# MedidorCO2_ver2.net
KiCad netlist of a schematic drawn in Altium Designer
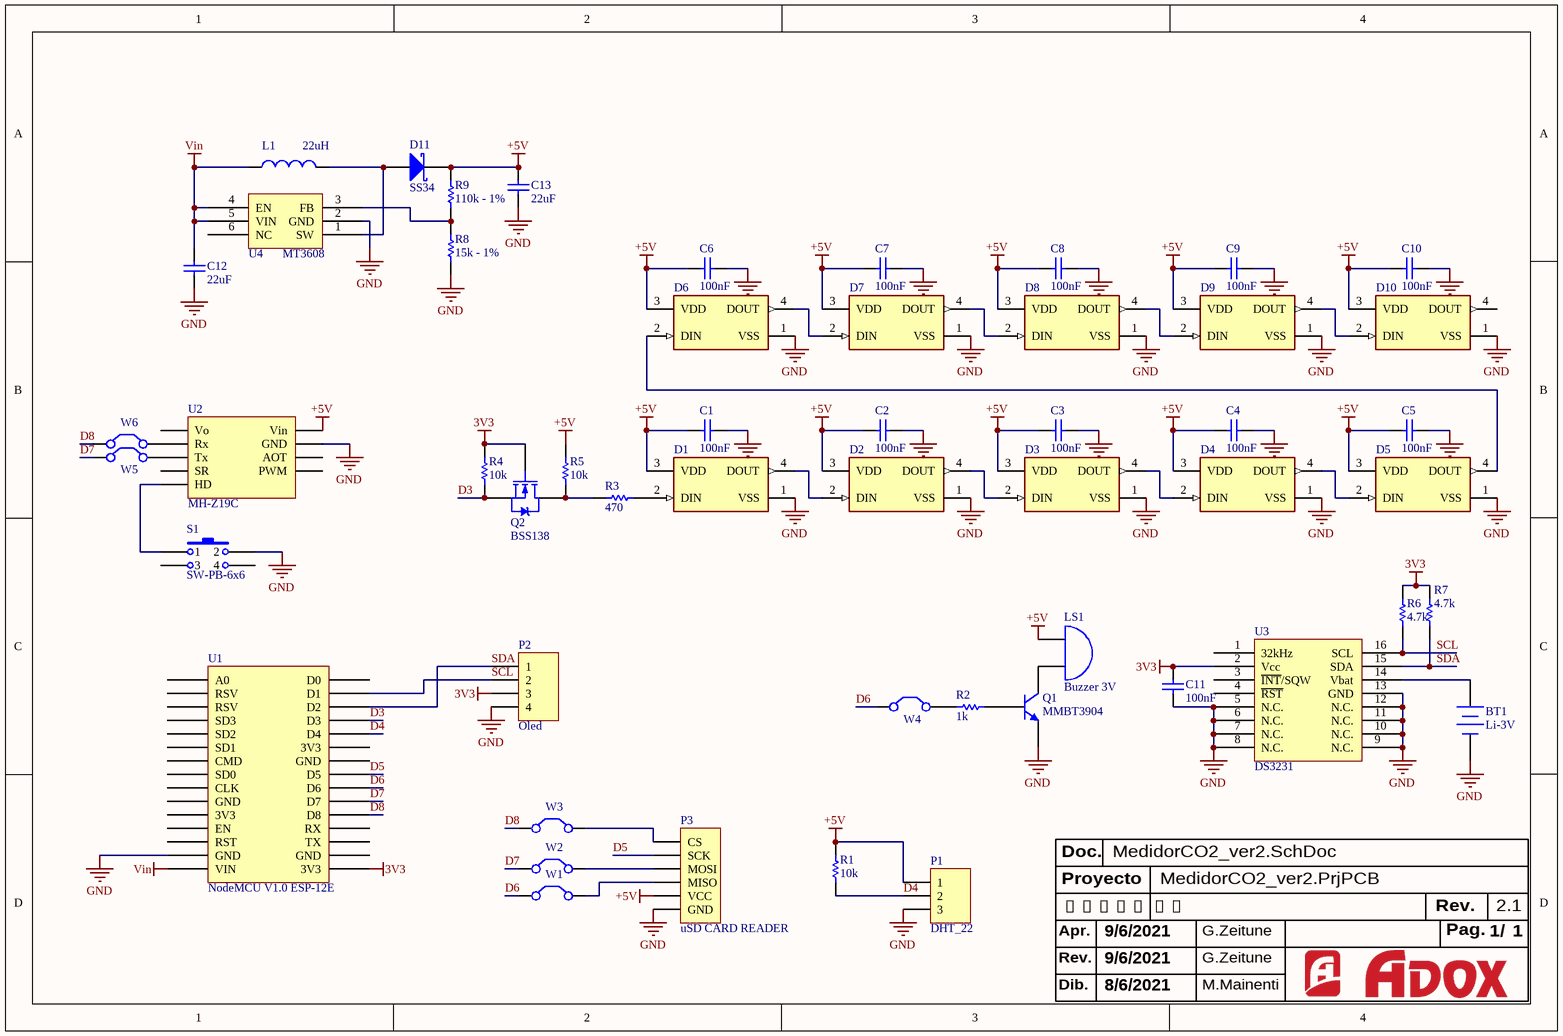
[diagram p0: MedidorCO2_ver2.SchDoc]

(export (version "E")
  (design (tool "Eeschema 10.0.6"))
  (components
    (comp (ref "BT1")
      (value "Li-3V")
      (footprint "BAT_LI_3V")
      (description "Multicell Battery")
      (fields (field (name "PUBLISHER") "Altium Limited"))
      (libsource (lib "Miscellaneous Devices") (part "Battery"))
    )
    (comp (ref "C1")
      (value "100nF")
      (footprint "CAPC2012N")
      (description "Capacitor (Semiconductor SIM Model)")
      (fields (field (name "PUBLISHER") "Altium Limited"))
      (libsource (lib "Miscellaneous Devices") (part "Cap Semi"))
    )
    (comp (ref "C2")
      (value "100nF")
      (footprint "CAPC2012N")
      (description "Capacitor (Semiconductor SIM Model)")
      (fields (field (name "PUBLISHER") "Altium Limited"))
      (libsource (lib "Miscellaneous Devices") (part "Cap Semi"))
    )
    (comp (ref "C3")
      (value "100nF")
      (footprint "CAPC2012N")
      (description "Capacitor (Semiconductor SIM Model)")
      (fields (field (name "PUBLISHER") "Altium Limited"))
      (libsource (lib "Miscellaneous Devices") (part "Cap Semi"))
    )
    (comp (ref "C4")
      (value "100nF")
      (footprint "CAPC2012N")
      (description "Capacitor (Semiconductor SIM Model)")
      (fields (field (name "PUBLISHER") "Altium Limited"))
      (libsource (lib "Miscellaneous Devices") (part "Cap Semi"))
    )
    (comp (ref "C5")
      (value "100nF")
      (footprint "CAPC2012N")
      (description "Capacitor (Semiconductor SIM Model)")
      (fields (field (name "PUBLISHER") "Altium Limited"))
      (libsource (lib "Miscellaneous Devices") (part "Cap Semi"))
    )
    (comp (ref "C6")
      (value "100nF")
      (footprint "CAPC2012N")
      (description "Capacitor (Semiconductor SIM Model)")
      (fields (field (name "PUBLISHER") "Altium Limited"))
      (libsource (lib "Miscellaneous Devices") (part "Cap Semi"))
    )
    (comp (ref "C7")
      (value "100nF")
      (footprint "CAPC2012N")
      (description "Capacitor (Semiconductor SIM Model)")
      (fields (field (name "PUBLISHER") "Altium Limited"))
      (libsource (lib "Miscellaneous Devices") (part "Cap Semi"))
    )
    (comp (ref "C8")
      (value "100nF")
      (footprint "CAPC2012N")
      (description "Capacitor (Semiconductor SIM Model)")
      (fields (field (name "PUBLISHER") "Altium Limited"))
      (libsource (lib "Miscellaneous Devices") (part "Cap Semi"))
    )
    (comp (ref "C9")
      (value "100nF")
      (footprint "CAPC2012N")
      (description "Capacitor (Semiconductor SIM Model)")
      (fields (field (name "PUBLISHER") "Altium Limited"))
      (libsource (lib "Miscellaneous Devices") (part "Cap Semi"))
    )
    (comp (ref "C10")
      (value "100nF")
      (footprint "CAPC2012N")
      (description "Capacitor (Semiconductor SIM Model)")
      (fields (field (name "PUBLISHER") "Altium Limited"))
      (libsource (lib "Miscellaneous Devices") (part "Cap Semi"))
    )
    (comp (ref "C11")
      (value "100nF")
      (footprint "CAPC2012N")
      (description "Capacitor (Semiconductor SIM Model)")
      (fields (field (name "PUBLISHER") "Altium Limited"))
      (libsource (lib "Miscellaneous Devices") (part "Cap Semi"))
    )
    (comp (ref "C12")
      (value "22uF")
      (footprint "CAPC3216N")
      (description "Capacitor (Semiconductor SIM Model)")
      (fields (field (name "PUBLISHER") "Altium Limited"))
      (libsource (lib "Miscellaneous Devices") (part "Cap Semi"))
    )
    (comp (ref "C13")
      (value "22uF")
      (footprint "CAPC3216N")
      (description "Capacitor (Semiconductor SIM Model)")
      (fields (field (name "PUBLISHER") "Altium Limited"))
      (libsource (lib "Miscellaneous Devices") (part "Cap Semi"))
    )
    (comp (ref "D1")
      (value "Neopixel_5050")
      (footprint "Neopixel_5050")
      (description "Adafruit Neopixel 5050 Addressable LED WS2812B/SK6812")
      (libsource (lib "Adox_Lib") (part "Neopixel_5050"))
    )
    (comp (ref "D2")
      (value "Neopixel_5050")
      (footprint "Neopixel_5050")
      (description "Adafruit Neopixel 5050 Addressable LED WS2812B/SK6812")
      (libsource (lib "Adox_Lib") (part "Neopixel_5050"))
    )
    (comp (ref "D3")
      (value "Neopixel_5050")
      (footprint "Neopixel_5050")
      (description "Adafruit Neopixel 5050 Addressable LED WS2812B/SK6812")
      (libsource (lib "Adox_Lib") (part "Neopixel_5050"))
    )
    (comp (ref "D4")
      (value "Neopixel_5050")
      (footprint "Neopixel_5050")
      (description "Adafruit Neopixel 5050 Addressable LED WS2812B/SK6812")
      (libsource (lib "Adox_Lib") (part "Neopixel_5050"))
    )
    (comp (ref "D5")
      (value "Neopixel_5050")
      (footprint "Neopixel_5050")
      (description "Adafruit Neopixel 5050 Addressable LED WS2812B/SK6812")
      (libsource (lib "Adox_Lib") (part "Neopixel_5050"))
    )
    (comp (ref "D6")
      (value "Neopixel_5050")
      (footprint "Neopixel_5050")
      (description "Adafruit Neopixel 5050 Addressable LED WS2812B/SK6812")
      (libsource (lib "Adox_Lib") (part "Neopixel_5050"))
    )
    (comp (ref "D7")
      (value "Neopixel_5050")
      (footprint "Neopixel_5050")
      (description "Adafruit Neopixel 5050 Addressable LED WS2812B/SK6812")
      (libsource (lib "Adox_Lib") (part "Neopixel_5050"))
    )
    (comp (ref "D8")
      (value "Neopixel_5050")
      (footprint "Neopixel_5050")
      (description "Adafruit Neopixel 5050 Addressable LED WS2812B/SK6812")
      (libsource (lib "Adox_Lib") (part "Neopixel_5050"))
    )
    (comp (ref "D9")
      (value "Neopixel_5050")
      (footprint "Neopixel_5050")
      (description "Adafruit Neopixel 5050 Addressable LED WS2812B/SK6812")
      (libsource (lib "Adox_Lib") (part "Neopixel_5050"))
    )
    (comp (ref "D10")
      (value "Neopixel_5050")
      (footprint "Neopixel_5050")
      (description "Adafruit Neopixel 5050 Addressable LED WS2812B/SK6812")
      (libsource (lib "Adox_Lib") (part "Neopixel_5050"))
    )
    (comp (ref "D11")
      (value "SS34")
      (footprint "SMC")
      (description "Schottky Diode SS34")
      (fields (field (name "PUBLISHER") "Altium Limited"))
      (libsource (lib "Miscellaneous Devices") (part "D Schottky"))
    )
    (comp (ref "L1")
      (value "22uH")
      (footprint "SMRH74-220MT")
      (description "Inductor SMRH74-220MT")
      (fields (field (name "PUBLISHER") "Altium Limited"))
      (libsource (lib "Miscellaneous Devices") (part "Inductor"))
    )
    (comp (ref "LS1")
      (value "Buzzer 3V")
      (footprint "BUZZER")
      (description "Electrical Bell")
      (fields (field (name "PUBLISHER") "Altium Limited"))
      (libsource (lib "Miscellaneous Devices") (part "Bell"))
    )
    (comp (ref "P1")
      (value "DHT_22")
      (footprint "CON1X3")
      (description "Header, 3-Pin")
      (fields (field (name "PUBLISHER") "Altium Limited"))
      (libsource (lib "Miscellaneous Connectors") (part "Header 3"))
    )
    (comp (ref "P2")
      (value "Oled")
      (footprint "HDR1X4")
      (description "Header, 4-Pin")
      (fields (field (name "PUBLISHER") "Altium Limited"))
      (libsource (lib "Miscellaneous Connectors") (part "Header 4"))
    )
    (comp (ref "P3")
      (value "uSD CARD READER")
      (footprint "HDR1X6")
      (description "Header, 6-Pin")
      (fields (field (name "PUBLISHER") "Altium Limited"))
      (libsource (lib "Miscellaneous Connectors") (part "Header 6"))
    )
    (comp (ref "Q1")
      (value "MMBT3904")
      (footprint "SOT23_N")
      (description "NPN Switching Transistor")
      (fields (field (name "PUBLISHER") "Altium Limited"))
      (libsource (lib "Philips Discrete BJT - Low Power") (part "MMBT3904"))
    )
    (comp (ref "Q2")
      (value "BSS138")
      (footprint "SOT-23_N")
      (description "N-Channel Power MOSFET")
      (fields (field (name "PUBLISHER") "Altium Limited"))
      (libsource (lib "Miscellaneous Devices") (part "NMOS-2"))
    )
    (comp (ref "R1")
      (value "10k")
      (footprint "RESC2012N")
      (description "Resistor")
      (fields (field (name "PUBLISHER") "Altium Limited"))
      (libsource (lib "Miscellaneous Devices") (part "Res1"))
    )
    (comp (ref "R2")
      (value "1k")
      (footprint "RESC2012N")
      (description "Resistor")
      (fields (field (name "PUBLISHER") "Altium Limited"))
      (libsource (lib "Miscellaneous Devices") (part "Res1"))
    )
    (comp (ref "R3")
      (value "470")
      (footprint "RESC2012N")
      (description "Resistor")
      (fields (field (name "PUBLISHER") "Altium Limited"))
      (libsource (lib "Miscellaneous Devices") (part "Res1"))
    )
    (comp (ref "R4")
      (value "10k")
      (footprint "RESC2012N")
      (description "Resistor")
      (fields (field (name "PUBLISHER") "Altium Limited"))
      (libsource (lib "Miscellaneous Devices") (part "Res1"))
    )
    (comp (ref "R5")
      (value "10k")
      (footprint "RESC2012N")
      (description "Resistor")
      (fields (field (name "PUBLISHER") "Altium Limited"))
      (libsource (lib "Miscellaneous Devices") (part "Res1"))
    )
    (comp (ref "R6")
      (value "4.7k")
      (footprint "RESC2012N")
      (description "Resistor")
      (fields (field (name "PUBLISHER") "Altium Limited"))
      (libsource (lib "Miscellaneous Devices") (part "Res1"))
    )
    (comp (ref "R7")
      (value "4.7k")
      (footprint "RESC2012N")
      (description "Resistor")
      (fields (field (name "PUBLISHER") "Altium Limited"))
      (libsource (lib "Miscellaneous Devices") (part "Res1"))
    )
    (comp (ref "R8")
      (value "15k - 1%")
      (footprint "RESC2012N")
      (description "Resistor")
      (fields (field (name "PUBLISHER") "Altium Limited"))
      (libsource (lib "Miscellaneous Devices") (part "Res1"))
    )
    (comp (ref "R9")
      (value "110k - 1%")
      (footprint "RESC2012N")
      (description "Resistor")
      (fields (field (name "PUBLISHER") "Altium Limited"))
      (libsource (lib "Miscellaneous Devices") (part "Res1"))
    )
    (comp (ref "S1")
      (value "SW-PB-6x6")
      (footprint "pulsador2")
      (description "Switch")
      (fields (field (name "PUBLISHER") "Altium Limited"))
      (libsource (lib "Adox_Lib") (part "SW-PB-6x6"))
    )
    (comp (ref "U1")
      (value "NodeMCU V1.0 ESP-12E")
      (footprint "NodeMCU V1.0 ESP-12E")
      (description "NodeMCU V1.0 ESP8266 (ESP-12E)")
      (libsource (lib "nodemcu") (part "NodeMCU V1.0 ESP-12E"))
    )
    (comp (ref "U2")
      (value "MH-Z19C")
      (footprint "MH-Z19C")
      (description "Sensor CO2")
      (libsource (lib "Adox_Lib") (part "MH-Z19C"))
    )
    (comp (ref "U3")
      (value "DS3231")
      (footprint "SOIC16 - DS3231")
      (description "Extremely Accurate I2C-Integrated  RTC/TCXO/Crystal")
      (libsource (lib "Adox_Lib") (part "DS3231"))
    )
    (comp (ref "U4")
      (value "MT3608")
      (footprint "SOT23-6")
      (description "Boost converter")
      (libsource (lib "Adox_Lib") (part "MT3608"))
    )
    (comp (ref "W1")
      (value "Jumper")
      (footprint "RESC1608N")
      (description "Jumper Wire")
      (fields (field (name "PUBLISHER") "Altium Limited"))
      (libsource (lib "Miscellaneous Devices") (part "Jumper"))
    )
    (comp (ref "W2")
      (value "Jumper")
      (footprint "RESC1608N")
      (description "Jumper Wire")
      (fields (field (name "PUBLISHER") "Altium Limited"))
      (libsource (lib "Miscellaneous Devices") (part "Jumper"))
    )
    (comp (ref "W3")
      (value "Jumper")
      (footprint "RESC1608N")
      (description "Jumper Wire")
      (fields (field (name "PUBLISHER") "Altium Limited"))
      (libsource (lib "Miscellaneous Devices") (part "Jumper"))
    )
    (comp (ref "W4")
      (value "Jumper")
      (footprint "RESC1608N")
      (description "Jumper Wire")
      (fields (field (name "PUBLISHER") "Altium Limited"))
      (libsource (lib "Miscellaneous Devices") (part "Jumper"))
    )
    (comp (ref "W5")
      (value "Jumper")
      (footprint "RESC1608N")
      (description "Jumper Wire")
      (fields (field (name "PUBLISHER") "Altium Limited"))
      (libsource (lib "Miscellaneous Devices") (part "Jumper"))
    )
    (comp (ref "W6")
      (value "Jumper")
      (footprint "RESC1608N")
      (description "Jumper Wire")
      (fields (field (name "PUBLISHER") "Altium Limited"))
      (libsource (lib "Miscellaneous Devices") (part "Jumper"))
    )
  )
  (nets
    (net (code "1") (name "+5V") (class "Default")
      (node (ref "C1") (pin "1") (pinfunction "1_1") (pintype "passive"))
      (node (ref "C10") (pin "1") (pinfunction "1_1") (pintype "passive"))
      (node (ref "C13") (pin "2") (pinfunction "2_2") (pintype "passive"))
      (node (ref "C2") (pin "1") (pinfunction "1_1") (pintype "passive"))
      (node (ref "C3") (pin "1") (pinfunction "1_1") (pintype "passive"))
      (node (ref "C4") (pin "1") (pinfunction "1_1") (pintype "passive"))
      (node (ref "C5") (pin "1") (pinfunction "1_1") (pintype "passive"))
      (node (ref "C6") (pin "1") (pinfunction "1_1") (pintype "passive"))
      (node (ref "C7") (pin "1") (pinfunction "1_1") (pintype "passive"))
      (node (ref "C8") (pin "1") (pinfunction "1_1") (pintype "passive"))
      (node (ref "C9") (pin "1") (pinfunction "1_1") (pintype "passive"))
      (node (ref "D1") (pin "3") (pinfunction "VDD_3") (pintype "power_in"))
      (node (ref "D10") (pin "3") (pinfunction "VDD_3") (pintype "power_in"))
      (node (ref "D11") (pin "2") (pinfunction "K_2") (pintype "passive"))
      (node (ref "D2") (pin "3") (pinfunction "VDD_3") (pintype "power_in"))
      (node (ref "D3") (pin "3") (pinfunction "VDD_3") (pintype "power_in"))
      (node (ref "D4") (pin "3") (pinfunction "VDD_3") (pintype "power_in"))
      (node (ref "D5") (pin "3") (pinfunction "VDD_3") (pintype "power_in"))
      (node (ref "D6") (pin "3") (pinfunction "VDD_3") (pintype "power_in"))
      (node (ref "D7") (pin "3") (pinfunction "VDD_3") (pintype "power_in"))
      (node (ref "D8") (pin "3") (pinfunction "VDD_3") (pintype "power_in"))
      (node (ref "D9") (pin "3") (pinfunction "VDD_3") (pintype "power_in"))
      (node (ref "LS1") (pin "1") (pinfunction "A_1") (pintype "passive"))
      (node (ref "P1") (pin "1") (pinfunction "1_1") (pintype "passive"))
      (node (ref "P3") (pin "5") (pinfunction "VCC_5") (pintype "passive"))
      (node (ref "R1") (pin "2") (pinfunction "2_2") (pintype "passive"))
      (node (ref "R5") (pin "2") (pinfunction "2_2") (pintype "passive"))
      (node (ref "R9") (pin "2") (pinfunction "2_2") (pintype "passive"))
      (node (ref "U2") (pin "Vin") (pinfunction "Vin_Vin") (pintype "passive"))
    )
    (net (code "2") (name "/D3") (class "Default")
      (node (ref "Q2") (pin "2") (pinfunction "S_2") (pintype "passive"))
      (node (ref "R4") (pin "1") (pinfunction "1_1") (pintype "passive"))
      (node (ref "U1") (pin "D3") (pinfunction "D3_D3") (pintype "passive"))
    )
    (net (code "3") (name "/D4") (class "Default")
      (node (ref "P1") (pin "2") (pinfunction "2_2") (pintype "passive"))
      (node (ref "R1") (pin "1") (pinfunction "1_1") (pintype "passive"))
      (node (ref "U1") (pin "D4") (pinfunction "D4_D4") (pintype "passive"))
    )
    (net (code "4") (name "/D5") (class "Default")
      (node (ref "P3") (pin "2") (pinfunction "SCK_2") (pintype "passive"))
      (node (ref "U1") (pin "D5") (pinfunction "D5_D5") (pintype "passive"))
    )
    (net (code "5") (name "/D6") (class "Default")
      (node (ref "U1") (pin "D6") (pinfunction "D6_D6") (pintype "passive"))
      (node (ref "W1") (pin "1") (pinfunction "C1_1") (pintype "passive"))
      (node (ref "W4") (pin "1") (pinfunction "C1_1") (pintype "passive"))
    )
    (net (code "6") (name "/D7") (class "Default")
      (node (ref "U1") (pin "D7") (pinfunction "D7_D7") (pintype "passive"))
      (node (ref "W2") (pin "1") (pinfunction "C1_1") (pintype "passive"))
      (node (ref "W5") (pin "1") (pinfunction "C1_1") (pintype "passive"))
    )
    (net (code "7") (name "/D8") (class "Default")
      (node (ref "U1") (pin "D8") (pinfunction "D8_D8") (pintype "passive"))
      (node (ref "W3") (pin "1") (pinfunction "C1_1") (pintype "passive"))
      (node (ref "W6") (pin "1") (pinfunction "C1_1") (pintype "passive"))
    )
    (net (code "8") (name "/SCL") (class "Default")
      (node (ref "P2") (pin "2") (pinfunction "2_2") (pintype "passive"))
      (node (ref "R6") (pin "1") (pinfunction "1_1") (pintype "passive"))
      (node (ref "U1") (pin "D1") (pinfunction "D1_D1") (pintype "passive"))
      (node (ref "U3") (pin "16") (pinfunction "SCL_16") (pintype "passive"))
    )
    (net (code "9") (name "/SDA") (class "Default")
      (node (ref "P2") (pin "1") (pinfunction "1_1") (pintype "passive"))
      (node (ref "R7") (pin "1") (pinfunction "1_1") (pintype "passive"))
      (node (ref "U1") (pin "D2") (pinfunction "D2_D2") (pintype "passive"))
      (node (ref "U3") (pin "15") (pinfunction "SDA_15") (pintype "passive"))
    )
    (net (code "10") (name "3V3") (class "Default")
      (node (ref "C11") (pin "1") (pinfunction "1_1") (pintype "passive"))
      (node (ref "P2") (pin "3") (pinfunction "3_3") (pintype "passive"))
      (node (ref "Q2") (pin "1") (pinfunction "G_1") (pintype "passive"))
      (node (ref "R4") (pin "2") (pinfunction "2_2") (pintype "passive"))
      (node (ref "R6") (pin "2") (pinfunction "2_2") (pintype "passive"))
      (node (ref "R7") (pin "2") (pinfunction "2_2") (pintype "passive"))
      (node (ref "U1") (pin "3V3") (pinfunction "3V3_3V3") (pintype "passive"))
      (node (ref "U3") (pin "2") (pinfunction "Vcc_2") (pintype "passive"))
    )
    (net (code "11") (name "GND") (class "Default")
      (node (ref "BT1") (pin "2") (pinfunction "-_2") (pintype "passive"))
      (node (ref "C1") (pin "2") (pinfunction "2_2") (pintype "passive"))
      (node (ref "C10") (pin "2") (pinfunction "2_2") (pintype "passive"))
      (node (ref "C11") (pin "2") (pinfunction "2_2") (pintype "passive"))
      (node (ref "C12") (pin "1") (pinfunction "1_1") (pintype "passive"))
      (node (ref "C13") (pin "1") (pinfunction "1_1") (pintype "passive"))
      (node (ref "C2") (pin "2") (pinfunction "2_2") (pintype "passive"))
      (node (ref "C3") (pin "2") (pinfunction "2_2") (pintype "passive"))
      (node (ref "C4") (pin "2") (pinfunction "2_2") (pintype "passive"))
      (node (ref "C5") (pin "2") (pinfunction "2_2") (pintype "passive"))
      (node (ref "C6") (pin "2") (pinfunction "2_2") (pintype "passive"))
      (node (ref "C7") (pin "2") (pinfunction "2_2") (pintype "passive"))
      (node (ref "C8") (pin "2") (pinfunction "2_2") (pintype "passive"))
      (node (ref "C9") (pin "2") (pinfunction "2_2") (pintype "passive"))
      (node (ref "D1") (pin "1") (pinfunction "VSS_1") (pintype "power_in"))
      (node (ref "D10") (pin "1") (pinfunction "VSS_1") (pintype "power_in"))
      (node (ref "D2") (pin "1") (pinfunction "VSS_1") (pintype "power_in"))
      (node (ref "D3") (pin "1") (pinfunction "VSS_1") (pintype "power_in"))
      (node (ref "D4") (pin "1") (pinfunction "VSS_1") (pintype "power_in"))
      (node (ref "D5") (pin "1") (pinfunction "VSS_1") (pintype "power_in"))
      (node (ref "D6") (pin "1") (pinfunction "VSS_1") (pintype "power_in"))
      (node (ref "D7") (pin "1") (pinfunction "VSS_1") (pintype "power_in"))
      (node (ref "D8") (pin "1") (pinfunction "VSS_1") (pintype "power_in"))
      (node (ref "D9") (pin "1") (pinfunction "VSS_1") (pintype "power_in"))
      (node (ref "P1") (pin "3") (pinfunction "3_3") (pintype "passive"))
      (node (ref "P2") (pin "4") (pinfunction "4_4") (pintype "passive"))
      (node (ref "P3") (pin "6") (pinfunction "GND_6") (pintype "passive"))
      (node (ref "Q1") (pin "2") (pinfunction "E_2") (pintype "passive"))
      (node (ref "R8") (pin "1") (pinfunction "1_1") (pintype "passive"))
      (node (ref "S1") (pin "2") (pinfunction "2_2") (pintype "passive"))
      (node (ref "U1") (pin "GND") (pinfunction "GND_GND") (pintype "passive"))
      (node (ref "U2") (pin "GND") (pinfunction "GND_GND") (pintype "passive"))
      (node (ref "U3") (pin "10") (pinfunction "N.C._10") (pintype "passive"))
      (node (ref "U3") (pin "11") (pinfunction "N.C._11") (pintype "passive"))
      (node (ref "U3") (pin "12") (pinfunction "N.C._12") (pintype "passive"))
      (node (ref "U3") (pin "13") (pinfunction "GND_13") (pintype "passive"))
      (node (ref "U3") (pin "5") (pinfunction "N.C._5") (pintype "passive"))
      (node (ref "U3") (pin "6") (pinfunction "N.C._6") (pintype "passive"))
      (node (ref "U3") (pin "7") (pinfunction "N.C._7") (pintype "passive"))
      (node (ref "U3") (pin "8") (pinfunction "N.C._8") (pintype "passive"))
      (node (ref "U3") (pin "9") (pinfunction "N.C._9") (pintype "passive"))
      (node (ref "U4") (pin "2") (pinfunction "GND_2") (pintype "passive"))
    )
    (net (code "12") (name "Net-(BT1-+)") (class "Default")
      (node (ref "BT1") (pin "1") (pinfunction "+_1") (pintype "passive"))
      (node (ref "U3") (pin "14") (pinfunction "Vbat_14") (pintype "passive"))
    )
    (net (code "13") (name "Net-(D1-DIN)") (class "Default")
      (node (ref "D1") (pin "2") (pinfunction "DIN_2") (pintype "input"))
      (node (ref "R3") (pin "2") (pinfunction "2_2") (pintype "passive"))
    )
    (net (code "14") (name "Net-(D1-DOUT)") (class "Default")
      (node (ref "D1") (pin "4") (pinfunction "DOUT_4") (pintype "output"))
      (node (ref "D2") (pin "2") (pinfunction "DIN_2") (pintype "input"))
    )
    (net (code "15") (name "Net-(D2-DOUT)") (class "Default")
      (node (ref "D2") (pin "4") (pinfunction "DOUT_4") (pintype "output"))
      (node (ref "D3") (pin "2") (pinfunction "DIN_2") (pintype "input"))
    )
    (net (code "16") (name "Net-(D3-DOUT)") (class "Default")
      (node (ref "D3") (pin "4") (pinfunction "DOUT_4") (pintype "output"))
      (node (ref "D4") (pin "2") (pinfunction "DIN_2") (pintype "input"))
    )
    (net (code "17") (name "Net-(D4-DOUT)") (class "Default")
      (node (ref "D4") (pin "4") (pinfunction "DOUT_4") (pintype "output"))
      (node (ref "D5") (pin "2") (pinfunction "DIN_2") (pintype "input"))
    )
    (net (code "18") (name "Net-(D5-DOUT)") (class "Default")
      (node (ref "D5") (pin "4") (pinfunction "DOUT_4") (pintype "output"))
      (node (ref "D6") (pin "2") (pinfunction "DIN_2") (pintype "input"))
    )
    (net (code "19") (name "Net-(D6-DOUT)") (class "Default")
      (node (ref "D6") (pin "4") (pinfunction "DOUT_4") (pintype "output"))
      (node (ref "D7") (pin "2") (pinfunction "DIN_2") (pintype "input"))
    )
    (net (code "20") (name "Net-(D7-DOUT)") (class "Default")
      (node (ref "D7") (pin "4") (pinfunction "DOUT_4") (pintype "output"))
      (node (ref "D8") (pin "2") (pinfunction "DIN_2") (pintype "input"))
    )
    (net (code "21") (name "Net-(D8-DOUT)") (class "Default")
      (node (ref "D8") (pin "4") (pinfunction "DOUT_4") (pintype "output"))
      (node (ref "D9") (pin "2") (pinfunction "DIN_2") (pintype "input"))
    )
    (net (code "22") (name "Net-(D10-DIN)") (class "Default")
      (node (ref "D10") (pin "2") (pinfunction "DIN_2") (pintype "input"))
      (node (ref "D9") (pin "4") (pinfunction "DOUT_4") (pintype "output"))
    )
    (net (code "23") (name "Net-(D11-A)") (class "Default")
      (node (ref "D11") (pin "1") (pinfunction "A_1") (pintype "passive"))
      (node (ref "L1") (pin "2") (pinfunction "2_2") (pintype "passive"))
      (node (ref "U4") (pin "1") (pinfunction "SW_1") (pintype "passive"))
    )
    (net (code "24") (name "Net-(LS1-B)") (class "Default")
      (node (ref "LS1") (pin "2") (pinfunction "B_2") (pintype "passive"))
      (node (ref "Q1") (pin "3") (pinfunction "C_3") (pintype "passive"))
    )
    (net (code "25") (name "Net-(P3-CS)") (class "Default")
      (node (ref "P3") (pin "1") (pinfunction "CS_1") (pintype "passive"))
      (node (ref "W3") (pin "2") (pinfunction "C2_2") (pintype "passive"))
    )
    (net (code "26") (name "Net-(P3-MISO)") (class "Default")
      (node (ref "P3") (pin "4") (pinfunction "MISO_4") (pintype "passive"))
      (node (ref "W1") (pin "2") (pinfunction "C2_2") (pintype "passive"))
    )
    (net (code "27") (name "Net-(P3-MOSI)") (class "Default")
      (node (ref "P3") (pin "3") (pinfunction "MOSI_3") (pintype "passive"))
      (node (ref "W2") (pin "2") (pinfunction "C2_2") (pintype "passive"))
    )
    (net (code "28") (name "Net-(Q1-B)") (class "Default")
      (node (ref "Q1") (pin "1") (pinfunction "B_1") (pintype "passive"))
      (node (ref "R2") (pin "2") (pinfunction "2_2") (pintype "passive"))
    )
    (net (code "29") (name "Net-(Q2-D)") (class "Default")
      (node (ref "Q2") (pin "3") (pinfunction "D_3") (pintype "passive"))
      (node (ref "R3") (pin "1") (pinfunction "1_1") (pintype "passive"))
      (node (ref "R5") (pin "1") (pinfunction "1_1") (pintype "passive"))
    )
    (net (code "30") (name "Net-(S1-Pad1)") (class "Default")
      (node (ref "S1") (pin "1") (pinfunction "1_1") (pintype "passive"))
      (node (ref "U2") (pin "HD") (pinfunction "HD_HD") (pintype "passive"))
    )
    (net (code "31") (name "Net-(U4-FB)") (class "Default")
      (node (ref "R8") (pin "2") (pinfunction "2_2") (pintype "passive"))
      (node (ref "R9") (pin "1") (pinfunction "1_1") (pintype "passive"))
      (node (ref "U4") (pin "3") (pinfunction "FB_3") (pintype "passive"))
    )
    (net (code "32") (name "Net-(W4-C2)") (class "Default")
      (node (ref "R2") (pin "1") (pinfunction "1_1") (pintype "passive"))
      (node (ref "W4") (pin "2") (pinfunction "C2_2") (pintype "passive"))
    )
    (net (code "33") (name "Net-(W5-C2)") (class "Default")
      (node (ref "U2") (pin "Tx") (pinfunction "Tx_Tx") (pintype "passive"))
      (node (ref "W5") (pin "2") (pinfunction "C2_2") (pintype "passive"))
    )
    (net (code "34") (name "Net-(W6-C2)") (class "Default")
      (node (ref "U2") (pin "Rx") (pinfunction "Rx_Rx") (pintype "passive"))
      (node (ref "W6") (pin "2") (pinfunction "C2_2") (pintype "passive"))
    )
    (net (code "35") (name "Vin") (class "Default")
      (node (ref "C12") (pin "2") (pinfunction "2_2") (pintype "passive"))
      (node (ref "L1") (pin "1") (pinfunction "1_1") (pintype "passive"))
      (node (ref "U1") (pin "VIN") (pinfunction "VIN_VIN") (pintype "passive"))
      (node (ref "U4") (pin "4") (pinfunction "EN_4") (pintype "passive"))
      (node (ref "U4") (pin "5") (pinfunction "VIN_5") (pintype "passive"))
    )
    (net (code "36") (name "unconnected-(D10-DOUT-Pad4)") (class "Default")
      (node (ref "D10") (pin "4") (pinfunction "DOUT_4") (pintype "output"))
    )
    (net (code "37") (name "unconnected-(S1-Pad3)") (class "Default")
      (node (ref "S1") (pin "3") (pinfunction "3_3") (pintype "passive"))
    )
    (net (code "38") (name "unconnected-(S1-Pad4)") (class "Default")
      (node (ref "S1") (pin "4") (pinfunction "4_4") (pintype "passive"))
    )
    (net (code "39") (name "unconnected-(U1-Pad3V3)") (class "Default")
      (node (ref "U1") (pin "3V3") (pinfunction "3V3_3V3") (pintype "passive"))
    )
    (net (code "40") (name "unconnected-(U1-Pad3V3)_1") (class "Default")
      (node (ref "U1") (pin "3V3") (pinfunction "3V3_3V3") (pintype "passive"))
    )
    (net (code "41") (name "unconnected-(U1-PadA0)") (class "Default")
      (node (ref "U1") (pin "A0") (pinfunction "A0_A0") (pintype "passive"))
    )
    (net (code "42") (name "unconnected-(U1-PadCLK)") (class "Default")
      (node (ref "U1") (pin "CLK") (pinfunction "CLK_CLK") (pintype "passive"))
    )
    (net (code "43") (name "unconnected-(U1-PadCMD)") (class "Default")
      (node (ref "U1") (pin "CMD") (pinfunction "CMD_CMD") (pintype "passive"))
    )
    (net (code "44") (name "unconnected-(U1-PadD0)") (class "Default")
      (node (ref "U1") (pin "D0") (pinfunction "D0_D0") (pintype "passive"))
    )
    (net (code "45") (name "unconnected-(U1-PadEN)") (class "Default")
      (node (ref "U1") (pin "EN") (pinfunction "EN_EN") (pintype "passive"))
    )
    (net (code "46") (name "unconnected-(U1-PadGND)") (class "Default")
      (node (ref "U1") (pin "GND") (pinfunction "GND_GND") (pintype "passive"))
    )
    (net (code "47") (name "unconnected-(U1-PadGND)_1") (class "Default")
      (node (ref "U1") (pin "GND") (pinfunction "GND_GND") (pintype "passive"))
    )
    (net (code "48") (name "unconnected-(U1-PadGND)_2") (class "Default")
      (node (ref "U1") (pin "GND") (pinfunction "GND_GND") (pintype "passive"))
    )
    (net (code "49") (name "unconnected-(U1-PadRST)") (class "Default")
      (node (ref "U1") (pin "RST") (pinfunction "RST_RST") (pintype "passive"))
    )
    (net (code "50") (name "unconnected-(U1-PadRSV)") (class "Default")
      (node (ref "U1") (pin "RSV") (pinfunction "RSV_RSV") (pintype "passive"))
    )
    (net (code "51") (name "unconnected-(U1-PadRSV)_1") (class "Default")
      (node (ref "U1") (pin "RSV") (pinfunction "RSV_RSV") (pintype "passive"))
    )
    (net (code "52") (name "unconnected-(U1-PadRX)") (class "Default")
      (node (ref "U1") (pin "RX") (pinfunction "RX_RX") (pintype "passive"))
    )
    (net (code "53") (name "unconnected-(U1-PadSD0)") (class "Default")
      (node (ref "U1") (pin "SD0") (pinfunction "SD0_SD0") (pintype "passive"))
    )
    (net (code "54") (name "unconnected-(U1-PadSD1)") (class "Default")
      (node (ref "U1") (pin "SD1") (pinfunction "SD1_SD1") (pintype "passive"))
    )
    (net (code "55") (name "unconnected-(U1-PadSD2)") (class "Default")
      (node (ref "U1") (pin "SD2") (pinfunction "SD2_SD2") (pintype "passive"))
    )
    (net (code "56") (name "unconnected-(U1-PadSD3)") (class "Default")
      (node (ref "U1") (pin "SD3") (pinfunction "SD3_SD3") (pintype "passive"))
    )
    (net (code "57") (name "unconnected-(U1-PadTX)") (class "Default")
      (node (ref "U1") (pin "TX") (pinfunction "TX_TX") (pintype "passive"))
    )
    (net (code "58") (name "unconnected-(U2-PadAOT)") (class "Default")
      (node (ref "U2") (pin "AOT") (pinfunction "AOT_AOT") (pintype "passive"))
    )
    (net (code "59") (name "unconnected-(U2-PadPWM)") (class "Default")
      (node (ref "U2") (pin "PWM") (pinfunction "PWM_PWM") (pintype "passive"))
    )
    (net (code "60") (name "unconnected-(U2-PadSR)") (class "Default")
      (node (ref "U2") (pin "SR") (pinfunction "SR_SR") (pintype "passive"))
    )
    (net (code "61") (name "unconnected-(U2-PadVo)") (class "Default")
      (node (ref "U2") (pin "Vo") (pinfunction "Vo_Vo") (pintype "passive"))
    )
    (net (code "62") (name "unconnected-(U3-32kHz-Pad1)") (class "Default")
      (node (ref "U3") (pin "1") (pinfunction "32kHz_1") (pintype "passive"))
    )
    (net (code "63") (name "unconnected-(U3-~{INT}{slash}SQW-Pad3)") (class "Default")
      (node (ref "U3") (pin "3") (pinfunction "~{INT}/SQW_3") (pintype "passive"))
    )
    (net (code "64") (name "unconnected-(U3-~{RST}-Pad4)") (class "Default")
      (node (ref "U3") (pin "4") (pinfunction "~{RST}_4") (pintype "passive"))
    )
    (net (code "65") (name "unconnected-(U4-NC-Pad6)") (class "Default")
      (node (ref "U4") (pin "6") (pinfunction "NC_6") (pintype "passive"))
    )
  )
)
